# 10_-_CPU_-_JTAG_CONTROL.net
KiCad netlist of a schematic drawn in Altium Designer
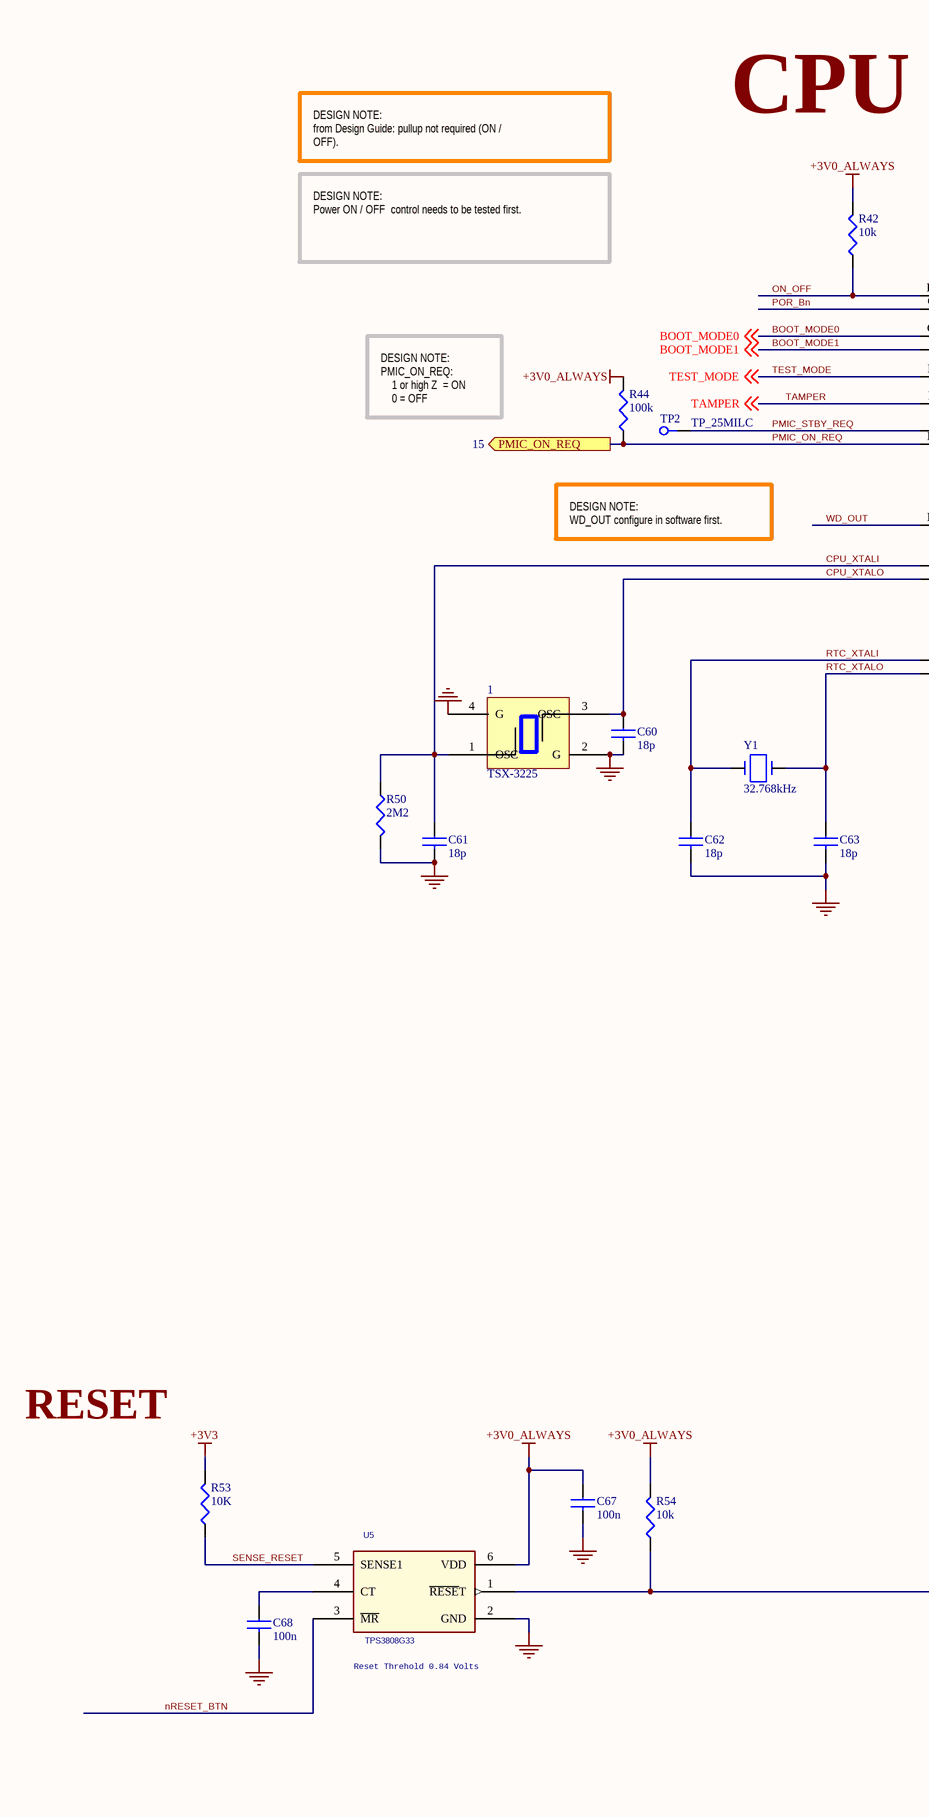
[diagram p0: [10] - CPU - JTAG, CONTROL.SchDoc, left]
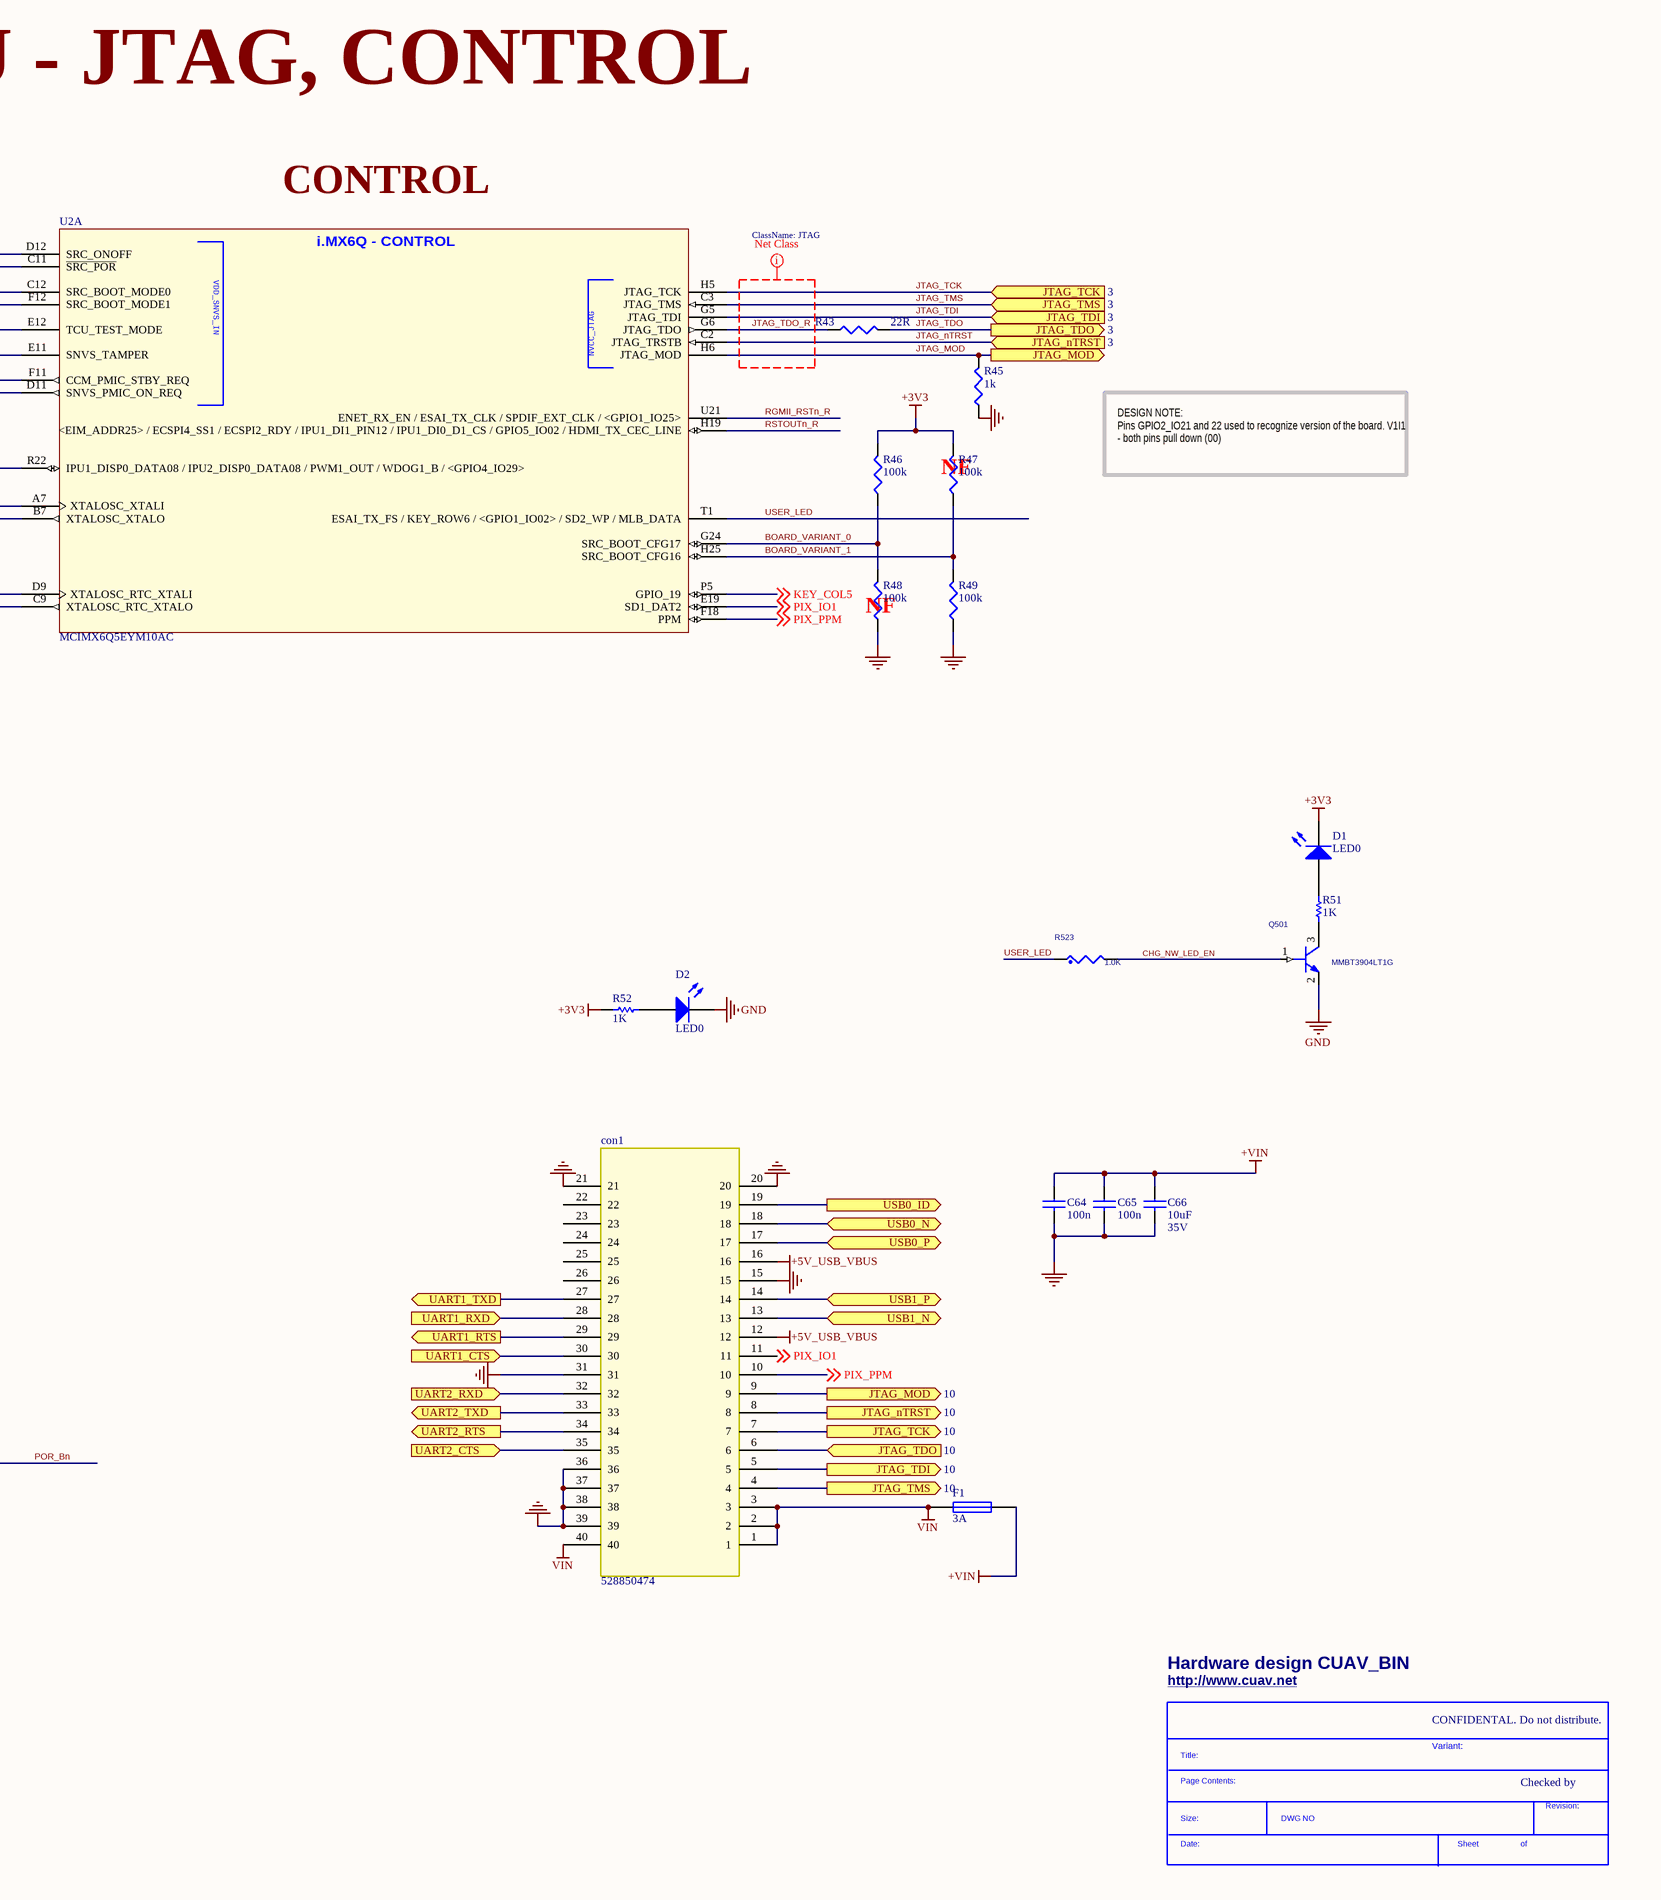
[diagram p1: [10] - CPU - JTAG, CONTROL.SchDoc, right]

(export (version "E")
  (design (tool "Eeschema 10.0.6"))
  (components
    (comp (ref "*") (value "SDTitleBlock") (libsource (lib "*") (part "SDTitleBlock")))
    (comp (ref "1") (value "TSX-3225") (footprint "TSX-3225") (libsource (lib "hack") (part "TSX-3225")))
    (comp (ref "C60")
      (value "18p")
      (footprint "0402cap")
      (description "CAP CER 18PF 50V C0G 5% 0402")
      (fields
        (field (name "MANUFACTURER") "TDK Corporation")
        (field (name "MANUFACTURER PART NUMBER") "C1005C0G1H180J")
      )
      (libsource (lib "Integrated_Library_RF_FEB_2012") (part "C1005C0G1H180J"))
    )
    (comp (ref "C61")
      (value "18p")
      (footprint "0402cap")
      (description "CAP CER 18PF 50V C0G 5% 0402")
      (fields
        (field (name "MANUFACTURER") "TDK Corporation")
        (field (name "MANUFACTURER PART NUMBER") "C1005C0G1H180J")
      )
      (libsource (lib "Integrated_Library_RF_FEB_2012") (part "C1005C0G1H180J"))
    )
    (comp (ref "C62")
      (value "18p")
      (footprint "0402cap")
      (description "CAP CER 18PF 50V C0G 5% 0402")
      (fields
        (field (name "MANUFACTURER") "TDK Corporation")
        (field (name "MANUFACTURER PART NUMBER") "C1005C0G1H180J")
      )
      (libsource (lib "Integrated_Library_RF_FEB_2012") (part "C1005C0G1H180J"))
    )
    (comp (ref "C63")
      (value "18p")
      (footprint "0402cap")
      (description "CAP CER 18PF 50V C0G 5% 0402")
      (fields
        (field (name "MANUFACTURER") "TDK Corporation")
        (field (name "MANUFACTURER PART NUMBER") "C1005C0G1H180J")
      )
      (libsource (lib "Integrated_Library_RF_FEB_2012") (part "C1005C0G1H180J"))
    )
    (comp (ref "C64")
      (value "100n")
      (footprint "0402CAP")
      (description "CAP CER .10UF 50V X5R 10% 0402")
      (fields
        (field (name "MANUFACTURER") "TDK Corporation")
        (field (name "MANUFACTURER PART NUMBER") "C1005X5R1H104K")
      )
      (libsource (lib "Integrated_Library_RF_FEB_2012") (part "C1005X5R1H104K"))
    )
    (comp (ref "C65")
      (value "100n")
      (footprint "0402CAP")
      (description "CAP CER .10UF 50V X5R 10% 0402")
      (fields
        (field (name "MANUFACTURER") "TDK Corporation")
        (field (name "MANUFACTURER PART NUMBER") "C1005X5R1H104K")
      )
      (libsource (lib "Integrated_Library_RF_FEB_2012") (part "C1005X5R1H104K"))
    )
    (comp (ref "C66")
      (value "10uF")
      (footprint "C1206A")
      (description "CAP CER 10UF 35V X5R 1206")
      (fields
        (field (name "MANUFACTURER") "Murata Electronics North America")
        (field (name "MANUFACTURER PART NUMBER") "GRM31CR6YA106KA12L")
        (field (name "VOLTAGE - RATED") "35V")
      )
      (libsource (lib "Integrated_Library_RF_FEB_2012") (part "GRM31CR6YA106KA12L"))
    )
    (comp (ref "C67")
      (value "100n")
      (footprint "0402cap")
      (description "CAP CER .10UF 50V X5R 10% 0402")
      (fields
        (field (name "MANUFACTURER") "TDK Corporation")
        (field (name "MANUFACTURER PART NUMBER") "C1005X5R1H104K")
      )
      (libsource (lib "Integrated_Library_RF_FEB_2012") (part "C1005X5R1H104K"))
    )
    (comp (ref "C68")
      (value "100n")
      (footprint "0402cap")
      (description "CAP CER .10UF 50V X5R 10% 0402")
      (fields
        (field (name "MANUFACTURER") "TDK Corporation")
        (field (name "MANUFACTURER PART NUMBER") "C1005X5R1H104K")
      )
      (libsource (lib "Integrated_Library_RF_FEB_2012") (part "C1005X5R1H104K"))
    )
    (comp (ref "con1")
      (value "528850474")
      (footprint "528850474")
      (libsource (lib "hack") (part "528850474"))
    )
    (comp (ref "D1")
      (value "LED0")
      (footprint "0603-led-b")
      (description "Typical INFRARED GaAs LED")
      (fields (field (name "PUBLISHER") "Altium Limited"))
      (libsource (lib "Miscellaneous Devices") (part "LED0"))
    )
    (comp (ref "D2")
      (value "LED0")
      (footprint "0603-led-b")
      (description "Typical INFRARED GaAs LED")
      (fields (field (name "PUBLISHER") "Altium Limited"))
      (libsource (lib "Miscellaneous Devices") (part "LED0"))
    )
    (comp (ref "F1")
      (value "3A")
      (footprint "0805L")
      (description "Fuse")
      (fields (field (name "PUBLISHER") "Altium Limited"))
      (libsource (lib "Miscellaneous Devices") (part "Fuse 1"))
    )
    (comp (ref "Q501")
      (value "MMBT3904LT1G")
      (description "TRAN NPN GEN 200MA 40V SOT-23")
      (libsource (lib "*") (part "NPN"))
    )
    (comp (ref "R42")
      (value "10k")
      (footprint "R0402")
      (description "RES 10.0K OHM 1/16W 1% 0402 SMD")
      (fields
        (field (name "MANUFACTURER") "Yageo")
        (field (name "MANUFACTURER PART NUMBER") "RC0402FR-0710KL")
      )
      (libsource (lib "Integrated_Library_RF_FEB_2012") (part "RC0402FR-0710KL"))
    )
    (comp (ref "R43")
      (value "22R")
      (footprint "R0402")
      (description "RES 22.0 OHM 1/16W 1% 0402 SMD")
      (fields
        (field (name "MANUFACTURER") "Yageo")
        (field (name "MANUFACTURER PART NUMBER") "RC0402FR-0722RL")
      )
      (libsource (lib "Integrated_Library_RF_FEB_2012") (part "RC0402FR-0722RL"))
    )
    (comp (ref "R44")
      (value "100k")
      (footprint "R0402")
      (description "RES 100K OHM 1/16W 1% 0402 SMD")
      (fields
        (field (name "MANUFACTURER") "Stackpole Electronics Inc")
        (field (name "MANUFACTURER PART NUMBER") "RMCF0402FT100K")
      )
      (libsource (lib "Integrated_Library_RF_FEB_2012") (part "RMCF0402FT100K"))
    )
    (comp (ref "R45")
      (value "1k")
      (footprint "R0402")
      (description "RES 1.00K OHM 1/16W 1% 0402 SMD")
      (fields
        (field (name "MANUFACTURER") "Yageo")
        (field (name "MANUFACTURER PART NUMBER") "RC0402FR-071KL")
      )
      (libsource (lib "Integrated_Library_RF_FEB_2012") (part "RC0402FR-071KL"))
    )
    (comp (ref "R46")
      (value "100k")
      (footprint "R0402")
      (description "RES 100K OHM 1/16W 1% 0402 SMD")
      (fields
        (field (name "MANUFACTURER") "Stackpole Electronics Inc")
        (field (name "MANUFACTURER PART NUMBER") "RMCF0402FT100K")
      )
      (libsource (lib "Integrated_Library_RF_FEB_2012") (part "RMCF0402FT100K"))
    )
    (comp (ref "R47")
      (value "100k")
      (footprint "R0402")
      (description "RES 100K OHM 1/16W 1% 0402 SMD")
      (fields
        (field (name "MANUFACTURER") "Stackpole Electronics Inc")
        (field (name "MANUFACTURER PART NUMBER") "RMCF0402FT100K")
      )
      (libsource (lib "Integrated_Library_RF_FEB_2012") (part "RMCF0402FT100K"))
    )
    (comp (ref "R48")
      (value "100k")
      (footprint "R0402")
      (description "RES 100K OHM 1/16W 1% 0402 SMD")
      (fields
        (field (name "MANUFACTURER") "Stackpole Electronics Inc")
        (field (name "MANUFACTURER PART NUMBER") "RMCF0402FT100K")
      )
      (libsource (lib "Integrated_Library_RF_FEB_2012") (part "RMCF0402FT100K"))
    )
    (comp (ref "R49")
      (value "100k")
      (footprint "R0402")
      (description "RES 100K OHM 1/16W 1% 0402 SMD")
      (fields
        (field (name "MANUFACTURER") "Stackpole Electronics Inc")
        (field (name "MANUFACTURER PART NUMBER") "RMCF0402FT100K")
      )
      (libsource (lib "Integrated_Library_RF_FEB_2012") (part "RMCF0402FT100K"))
    )
    (comp (ref "R50")
      (value "2M2")
      (footprint "R0402")
      (description "RES 2.20M OHM 1/16W 1% 0402 SMD")
      (fields
        (field (name "MANUFACTURER") "Vishay Dale")
        (field (name "MANUFACTURER PART NUMBER") "CRCW04022M20FKED")
        (field (name ".CREATOR") "MM")
      )
      (libsource (lib "Integrated_Library_RF_FEB_2012") (part "CRCW04022M20FKED"))
    )
    (comp (ref "R51")
      (value "1K")
      (footprint "R0402")
      (description "Resistor")
      (fields (field (name "PUBLISHER") "Altium Limited"))
      (libsource (lib "Miscellaneous Devices") (part "Res1"))
    )
    (comp (ref "R52")
      (value "1K")
      (footprint "R0402")
      (description "Resistor")
      (fields (field (name "PUBLISHER") "Altium Limited"))
      (libsource (lib "Miscellaneous Devices") (part "Res1"))
    )
    (comp (ref "R53")
      (value "10K")
      (footprint "R0402")
      (description "RES TF 4.99K OHM 1% 1/16W 0402")
      (fields
        (field (name "MANUFACTURER") "Stackpole Electronics Inc")
        (field (name "MANUFACTURER PART NUMBER") "RMCF0402FT4K99")
      )
      (libsource (lib "Integrated_Library_RF_FEB_2012") (part "RMCF0402FT4K99"))
    )
    (comp (ref "R54")
      (value "10k")
      (footprint "R0402")
      (description "RES 10.0K OHM 1/16W 1% 0402 SMD")
      (fields
        (field (name "MANUFACTURER") "Yageo")
        (field (name "MANUFACTURER PART NUMBER") "RC0402FR-0710KL")
      )
      (libsource (lib "Integrated_Library_RF_FEB_2012") (part "RC0402FR-0710KL"))
    )
    (comp (ref "R523")
      (value "1.0K")
      (description "RES MF 1.0K 1/16W 1% 0402")
      (fields (field (name "TOLERANCE") "1%"))
      (libsource (lib "*") (part "RES"))
    )
    (comp (ref "TP2")
      (value "TP_25MILC")
      (footprint "TP_25C")
      (description "Test Point 25mil")
      (libsource (lib "Integrated_Library_RF_FEB_2012") (part "TP_25MILC"))
    )
    (comp (ref "U2")
      (value "MCIMX6Q5EYM10AC")
      (footprint "PBGA624")
      (description "IC MCU 32BIT ARM QUAD 624FCBGA")
      (fields
        (field (name "MANUFACTURER") "Freescale Semiconductor")
        (field (name ".CREATOR") "MM")
        (field (name ".CHECKED PCB") "MM, checked by RF")
        (field (name ".CHECKED SCH") "MM")
      )
      (libsource (lib "Schlib_RF") (part "MCIMX6Q5EYM10AC"))
    )
    (comp (ref "U5")
      (value "TPS3808G33")
      (footprint "SOT-23-6")
      (description "IC VOLT SUPERVISOR 0.9V SOT23-6")
      (fields (field (name "PART #") "102020-0009R") (field (name "MANUFACTURER") "Texas Instruments"))
      (libsource (lib "Integrated_Library_RF_FEB_2012") (part "TPS3808G09DBVR"))
    )
    (comp (ref "Y1")
      (value "32.768kHz")
      (footprint "ABS06")
      (description "CRYSTAL 32.768 KHZ 9.0 PF SMD")
      (fields
        (field (name "MANUFACTURER") "Abracon Corporation")
        (field (name "MANUFACTURER PART NUMBER") "ABS06-32.768KHZ-9-1-T")
      )
      (libsource (lib "Integrated_Library_RF_FEB_2012") (part "ABS06-32.768KHZ-9-1-T"))
    )
  )
  (nets
    (net (code "1") (name "+3V0_ALWAYS") (class "Default")
      (node (ref "C67") (pin "1") (pinfunction "1_1") (pintype "passive"))
      (node (ref "R42") (pin "2") (pinfunction "2_2") (pintype "passive"))
      (node (ref "R44") (pin "2") (pinfunction "2_2") (pintype "passive"))
      (node (ref "R54") (pin "2") (pinfunction "2_2") (pintype "passive"))
      (node (ref "U5") (pin "6") (pinfunction "VDD_6") (pintype "passive"))
    )
    (net (code "2") (name "+3V3") (class "Default")
      (node (ref "D1") (pin "2") (pinfunction "2_2") (pintype "passive"))
      (node (ref "R46") (pin "2") (pinfunction "2_2") (pintype "passive"))
      (node (ref "R47") (pin "2") (pinfunction "2_2") (pintype "passive"))
      (node (ref "R52") (pin "2") (pinfunction "2_2") (pintype "passive"))
      (node (ref "R53") (pin "2") (pinfunction "2_2") (pintype "passive"))
    )
    (net (code "3") (name "+5V_USB_VBUS") (class "Default")
      (node (ref "con1") (pin "12") (pinfunction "12_12") (pintype "passive"))
      (node (ref "con1") (pin "16") (pinfunction "16_16") (pintype "passive"))
    )
    (net (code "4") (name "+VIN") (class "Default")
      (node (ref "C64") (pin "1") (pinfunction "1_1") (pintype "passive"))
      (node (ref "C65") (pin "1") (pinfunction "1_1") (pintype "passive"))
      (node (ref "C66") (pin "1") (pinfunction "1_1") (pintype "passive"))
      (node (ref "F1") (pin "2") (pinfunction "2_2") (pintype "passive"))
    )
    (net (code "5") (name "/BOARD_VARIANT_0") (class "Default")
      (node (ref "R46") (pin "1") (pinfunction "1_1") (pintype "passive"))
      (node (ref "R48") (pin "2") (pinfunction "2_2") (pintype "passive"))
      (node (ref "U2") (pin "G24") (pinfunction "SRC_BOOT_CFG17_G24") (pintype "bidirectional"))
    )
    (net (code "6") (name "/BOARD_VARIANT_1") (class "Default")
      (node (ref "R47") (pin "1") (pinfunction "1_1") (pintype "passive"))
      (node (ref "R49") (pin "2") (pinfunction "2_2") (pintype "passive"))
      (node (ref "U2") (pin "H25") (pinfunction "SRC_BOOT_CFG16_H25") (pintype "bidirectional"))
    )
    (net (code "7") (name "/CHG_NW_LED_EN") (class "Default")
      (node (ref "Q501") (pin "1") (pinfunction "BASE_1") (pintype "input"))
      (node (ref "R523") (pin "2") (pinfunction "2_2") (pintype "passive"))
    )
    (net (code "8") (name "/CPU_XTALI") (class "Default")
      (node (ref "1") (pin "1") (pinfunction "OSC_1") (pintype "passive"))
      (node (ref "C61") (pin "1") (pinfunction "1_1") (pintype "passive"))
      (node (ref "R50") (pin "1") (pinfunction "1_1") (pintype "passive"))
      (node (ref "U2") (pin "A7") (pinfunction "XTALOSC_XTALI_A7") (pintype "passive"))
    )
    (net (code "9") (name "/CPU_XTALO") (class "Default")
      (node (ref "1") (pin "3") (pinfunction "OSC_3") (pintype "passive"))
      (node (ref "C60") (pin "1") (pinfunction "1_1") (pintype "passive"))
      (node (ref "U2") (pin "B7") (pinfunction "XTALOSC_XTALO_B7") (pintype "output"))
    )
    (net (code "10") (name "/JTAG_MOD") (class "Default")
      (node (ref "R45") (pin "2") (pinfunction "2_2") (pintype "passive"))
      (node (ref "U2") (pin "H6") (pinfunction "JTAG_MOD_H6") (pintype "passive"))
      (node (ref "con1") (pin "9") (pinfunction "9_9") (pintype "passive"))
    )
    (net (code "11") (name "/JTAG_TCK") (class "Default")
      (node (ref "U2") (pin "H5") (pinfunction "JTAG_TCK_H5") (pintype "passive"))
      (node (ref "con1") (pin "7") (pinfunction "7_7") (pintype "passive"))
    )
    (net (code "12") (name "/JTAG_TDI") (class "Default")
      (node (ref "U2") (pin "G5") (pinfunction "JTAG_TDI_G5") (pintype "passive"))
      (node (ref "con1") (pin "5") (pinfunction "5_5") (pintype "passive"))
    )
    (net (code "13") (name "/JTAG_TDO") (class "Default")
      (node (ref "R43") (pin "2") (pinfunction "2_2") (pintype "passive"))
      (node (ref "con1") (pin "6") (pinfunction "6_6") (pintype "passive"))
    )
    (net (code "14") (name "/JTAG_TDO_R") (class "Default")
      (node (ref "R43") (pin "1") (pinfunction "1_1") (pintype "passive"))
      (node (ref "U2") (pin "G6") (pinfunction "JTAG_TDO_G6") (pintype "output"))
    )
    (net (code "15") (name "/JTAG_TMS") (class "Default")
      (node (ref "U2") (pin "C3") (pinfunction "JTAG_TMS_C3") (pintype "input"))
      (node (ref "con1") (pin "4") (pinfunction "4_4") (pintype "passive"))
    )
    (net (code "16") (name "/JTAG_nTRST") (class "Default")
      (node (ref "U2") (pin "C2") (pinfunction "JTAG_TRSTB_C2") (pintype "input"))
      (node (ref "con1") (pin "8") (pinfunction "8_8") (pintype "passive"))
    )
    (net (code "17") (name "/ON_OFF") (class "Default")
      (node (ref "R42") (pin "1") (pinfunction "1_1") (pintype "passive"))
      (node (ref "U2") (pin "D12") (pinfunction "SRC_ONOFF_D12") (pintype "passive"))
    )
    (net (code "18") (name "/PMIC_ON_REQ") (class "Default")
      (node (ref "R44") (pin "1") (pinfunction "1_1") (pintype "passive"))
      (node (ref "U2") (pin "D11") (pinfunction "SNVS_PMIC_ON_REQ_D11") (pintype "output"))
    )
    (net (code "19") (name "/PMIC_STBY_REQ") (class "Default")
      (node (ref "TP2") (pin "1") (pinfunction "1_1") (pintype "passive"))
      (node (ref "U2") (pin "F11") (pinfunction "CCM_PMIC_STBY_REQ_F11") (pintype "output"))
    )
    (net (code "20") (name "/POR_Bn") (class "Default")
      (node (ref "R54") (pin "1") (pinfunction "1_1") (pintype "passive"))
      (node (ref "U2") (pin "C11") (pinfunction "~{SRC_POR}_C11") (pintype "passive"))
      (node (ref "U5") (pin "1") (pinfunction "~{RESE}T_1") (pintype "output"))
    )
    (net (code "21") (name "/RGMII_RSTn_R") (class "Default")
      (node (ref "U2") (pin "U21") (pinfunction "ENET_RX_EN_/_ESAI_TX_CLK_/_SPDIF_EXT_CLK_/_<GPIO1_IO25>_U21") (pintype "passive"))
    )
    (net (code "22") (name "/RSTOUTn_R") (class "Default")
      (node (ref "U2") (pin "H19") (pinfunction "<EIM_ADDR25>_/_ECSPI4_SS1_/_ECSPI2_RDY_/_IPU1_DI1_PIN12_/_IPU1_DI0_D1_CS_/_GPIO5_IO02_/_HDMI_TX_CEC_LINE_H19") (pintype "bidirectional"))
    )
    (net (code "23") (name "/RTC_XTALI") (class "Default")
      (node (ref "C62") (pin "1") (pinfunction "1_1") (pintype "passive"))
      (node (ref "U2") (pin "D9") (pinfunction "XTALOSC_RTC_XTALI_D9") (pintype "passive"))
      (node (ref "Y1") (pin "1") (pinfunction "1_1") (pintype "passive"))
    )
    (net (code "24") (name "/RTC_XTALO") (class "Default")
      (node (ref "C63") (pin "1") (pinfunction "1_1") (pintype "passive"))
      (node (ref "U2") (pin "C9") (pinfunction "XTALOSC_RTC_XTALO_C9") (pintype "output"))
      (node (ref "Y1") (pin "2") (pinfunction "2_2") (pintype "passive"))
    )
    (net (code "25") (name "/SENSE_RESET") (class "Default")
      (node (ref "R53") (pin "1") (pinfunction "1_1") (pintype "passive"))
      (node (ref "U5") (pin "5") (pinfunction "SENSE1_5") (pintype "passive"))
    )
    (net (code "26") (name "/UART1_CTS") (class "Default")
      (node (ref "con1") (pin "30") (pinfunction "30_30") (pintype "passive"))
    )
    (net (code "27") (name "/UART1_RTS") (class "Default")
      (node (ref "con1") (pin "29") (pinfunction "29_29") (pintype "passive"))
    )
    (net (code "28") (name "/UART1_RXD") (class "Default")
      (node (ref "con1") (pin "28") (pinfunction "28_28") (pintype "passive"))
    )
    (net (code "29") (name "/UART1_TXD") (class "Default")
      (node (ref "con1") (pin "27") (pinfunction "27_27") (pintype "passive"))
    )
    (net (code "30") (name "/UART2_CTS") (class "Default")
      (node (ref "con1") (pin "35") (pinfunction "35_35") (pintype "passive"))
    )
    (net (code "31") (name "/UART2_RTS") (class "Default")
      (node (ref "con1") (pin "34") (pinfunction "34_34") (pintype "passive"))
    )
    (net (code "32") (name "/UART2_RXD") (class "Default")
      (node (ref "con1") (pin "32") (pinfunction "32_32") (pintype "passive"))
    )
    (net (code "33") (name "/UART2_TXD") (class "Default")
      (node (ref "con1") (pin "33") (pinfunction "33_33") (pintype "passive"))
    )
    (net (code "34") (name "/USB0_ID") (class "Default")
      (node (ref "con1") (pin "19") (pinfunction "19_19") (pintype "passive"))
    )
    (net (code "35") (name "/USB0_N") (class "Default")
      (node (ref "con1") (pin "18") (pinfunction "18_18") (pintype "passive"))
    )
    (net (code "36") (name "/USB0_P") (class "Default")
      (node (ref "con1") (pin "17") (pinfunction "17_17") (pintype "passive"))
    )
    (net (code "37") (name "/USB1_N") (class "Default")
      (node (ref "con1") (pin "13") (pinfunction "13_13") (pintype "passive"))
    )
    (net (code "38") (name "/USB1_P") (class "Default")
      (node (ref "con1") (pin "14") (pinfunction "14_14") (pintype "passive"))
    )
    (net (code "39") (name "/USER_LED") (class "Default")
      (node (ref "R523") (pin "1") (pinfunction "1_1") (pintype "passive"))
      (node (ref "U2") (pin "T1") (pinfunction "ESAI_TX_FS_/_KEY_ROW6_/_<GPIO1_IO02>_/_SD2_WP_/_MLB_DATA_T1") (pintype "passive"))
    )
    (net (code "40") (name "/WD_OUT") (class "Default")
      (node (ref "U2") (pin "R22") (pinfunction "IPU1_DISP0_DATA08_/_IPU2_DISP0_DATA08_/_PWM1_OUT_/_WDOG1_B_/_<GPIO4_IO29>_R22") (pintype "bidirectional"))
    )
    (net (code "41") (name "/nRESET_BTN") (class "Default")
      (node (ref "U5") (pin "3") (pinfunction "~{MR}_3") (pintype "passive"))
    )
    (net (code "42") (name "BOOT_MODE0") (class "Default")
      (node (ref "U2") (pin "C12") (pinfunction "SRC_BOOT_MODE0_C12") (pintype "passive"))
    )
    (net (code "43") (name "BOOT_MODE1") (class "Default")
      (node (ref "U2") (pin "F12") (pinfunction "SRC_BOOT_MODE1_F12") (pintype "passive"))
    )
    (net (code "44") (name "GND") (class "Default")
      (node (ref "1") (pin "2") (pinfunction "G_2") (pintype "passive"))
      (node (ref "1") (pin "4") (pinfunction "G_4") (pintype "passive"))
      (node (ref "C60") (pin "2") (pinfunction "2_2") (pintype "passive"))
      (node (ref "C61") (pin "2") (pinfunction "2_2") (pintype "passive"))
      (node (ref "C62") (pin "2") (pinfunction "2_2") (pintype "passive"))
      (node (ref "C63") (pin "2") (pinfunction "2_2") (pintype "passive"))
      (node (ref "C64") (pin "2") (pinfunction "2_2") (pintype "passive"))
      (node (ref "C65") (pin "2") (pinfunction "2_2") (pintype "passive"))
      (node (ref "C66") (pin "2") (pinfunction "2_2") (pintype "passive"))
      (node (ref "C67") (pin "2") (pinfunction "2_2") (pintype "passive"))
      (node (ref "C68") (pin "2") (pinfunction "2_2") (pintype "passive"))
      (node (ref "D2") (pin "2") (pinfunction "2_2") (pintype "passive"))
      (node (ref "Q501") (pin "2") (pinfunction "EMITTER_2") (pintype "passive"))
      (node (ref "R45") (pin "1") (pinfunction "1_1") (pintype "passive"))
      (node (ref "R48") (pin "1") (pinfunction "1_1") (pintype "passive"))
      (node (ref "R49") (pin "1") (pinfunction "1_1") (pintype "passive"))
      (node (ref "R50") (pin "2") (pinfunction "2_2") (pintype "passive"))
      (node (ref "U5") (pin "2") (pinfunction "GND_2") (pintype "passive"))
      (node (ref "con1") (pin "15") (pinfunction "15_15") (pintype "passive"))
      (node (ref "con1") (pin "20") (pinfunction "20_20") (pintype "passive"))
      (node (ref "con1") (pin "21") (pinfunction "21_21") (pintype "passive"))
      (node (ref "con1") (pin "31") (pinfunction "31_31") (pintype "passive"))
      (node (ref "con1") (pin "36") (pinfunction "36_36") (pintype "passive"))
      (node (ref "con1") (pin "37") (pinfunction "37_37") (pintype "passive"))
      (node (ref "con1") (pin "38") (pinfunction "38_38") (pintype "passive"))
      (node (ref "con1") (pin "39") (pinfunction "39_39") (pintype "passive"))
    )
    (net (code "45") (name "KEY_COL5") (class "Default")
      (node (ref "U2") (pin "P5") (pinfunction "GPIO_19_P5") (pintype "bidirectional"))
    )
    (net (code "46") (name "Net-(D1-Pad1)") (class "Default")
      (node (ref "D1") (pin "1") (pinfunction "1_1") (pintype "passive"))
      (node (ref "R51") (pin "1") (pinfunction "1_1") (pintype "passive"))
    )
    (net (code "47") (name "Net-(D2-Pad1)") (class "Default")
      (node (ref "D2") (pin "1") (pinfunction "1_1") (pintype "passive"))
      (node (ref "R52") (pin "1") (pinfunction "1_1") (pintype "passive"))
    )
    (net (code "48") (name "Net-(Q501-COLLECTOR)") (class "Default")
      (node (ref "Q501") (pin "3") (pinfunction "COLLECTOR_3") (pintype "passive"))
      (node (ref "R51") (pin "2") (pinfunction "2_2") (pintype "passive"))
    )
    (net (code "49") (name "Net-(U5-CT)") (class "Default")
      (node (ref "C68") (pin "1") (pinfunction "1_1") (pintype "passive"))
      (node (ref "U5") (pin "4") (pinfunction "CT_4") (pintype "passive"))
    )
    (net (code "50") (name "PIX_IO1") (class "Default")
      (node (ref "U2") (pin "E19") (pinfunction "SD1_DAT2_E19") (pintype "bidirectional"))
      (node (ref "con1") (pin "11") (pinfunction "11_11") (pintype "passive"))
    )
    (net (code "51") (name "PIX_PPM") (class "Default")
      (node (ref "U2") (pin "F18") (pinfunction "PPM_F18") (pintype "bidirectional"))
      (node (ref "con1") (pin "10") (pinfunction "10_10") (pintype "passive"))
    )
    (net (code "52") (name "TAMPER") (class "Default")
      (node (ref "U2") (pin "E11") (pinfunction "SNVS_TAMPER_E11") (pintype "passive"))
    )
    (net (code "53") (name "TEST_MODE") (class "Default")
      (node (ref "U2") (pin "E12") (pinfunction "TCU_TEST_MODE_E12") (pintype "passive"))
    )
    (net (code "54") (name "VIN") (class "Default")
      (node (ref "F1") (pin "1") (pinfunction "1_1") (pintype "passive"))
      (node (ref "con1") (pin "1") (pinfunction "1_1") (pintype "passive"))
      (node (ref "con1") (pin "2") (pinfunction "2_2") (pintype "passive"))
      (node (ref "con1") (pin "3") (pinfunction "3_3") (pintype "passive"))
      (node (ref "con1") (pin "40") (pinfunction "40_40") (pintype "passive"))
    )
    (net (code "55") (name "unconnected-(con1-Pad22)") (class "Default")
      (node (ref "con1") (pin "22") (pinfunction "22_22") (pintype "passive"))
    )
    (net (code "56") (name "unconnected-(con1-Pad23)") (class "Default")
      (node (ref "con1") (pin "23") (pinfunction "23_23") (pintype "passive"))
    )
    (net (code "57") (name "unconnected-(con1-Pad24)") (class "Default")
      (node (ref "con1") (pin "24") (pinfunction "24_24") (pintype "passive"))
    )
    (net (code "58") (name "unconnected-(con1-Pad25)") (class "Default")
      (node (ref "con1") (pin "25") (pinfunction "25_25") (pintype "passive"))
    )
    (net (code "59") (name "unconnected-(con1-Pad26)") (class "Default")
      (node (ref "con1") (pin "26") (pinfunction "26_26") (pintype "passive"))
    )
  )
)
